# SCH_gravmaskin_mottagare_2024-06-04.net
KiCad netlist of a schematic drawn in EasyEDA
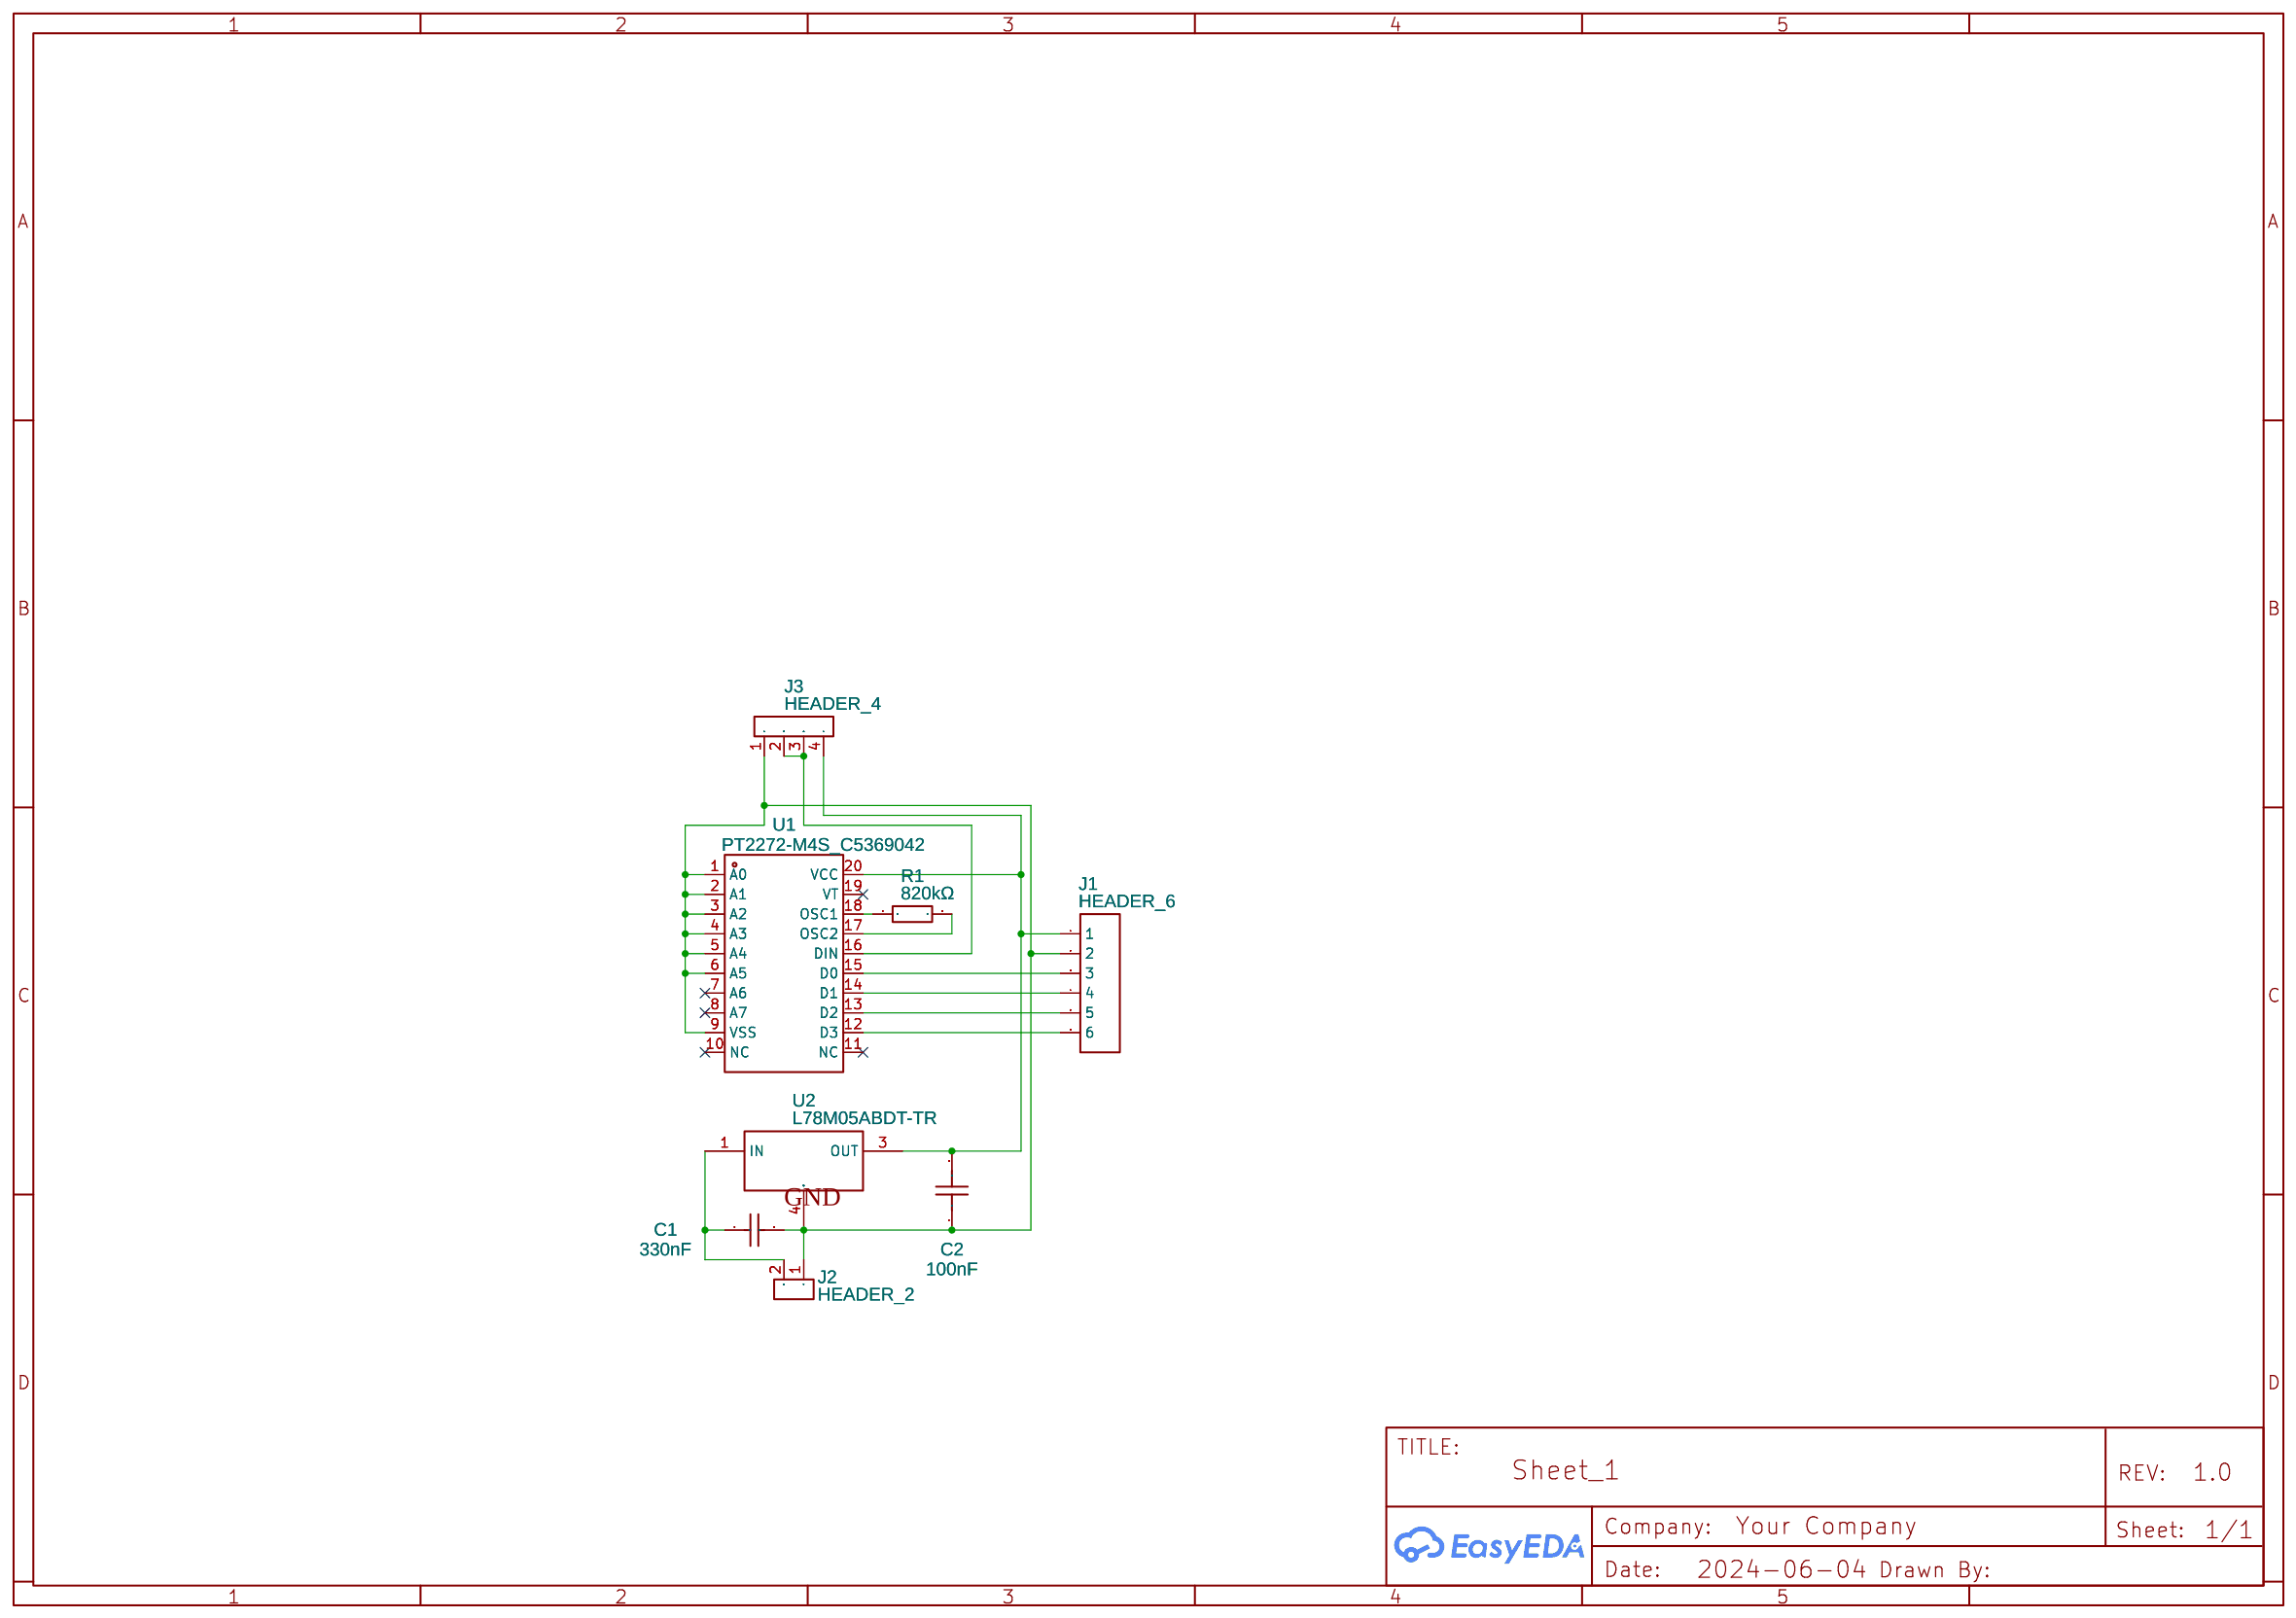
[diagram p0: schematic sheet]

(export (version "E")
  (design (tool "Eeschema 10.0.6"))
  (components
    (comp (ref "C1")
      (value "330nF")
      (fields (field (name "Manufacturer Part") "0603B334K250NT") (field (name "Manufacturer") "FH(风华)"))
      (libsource (lib "") (part "0603B334K250NT"))
    )
    (comp (ref "C2")
      (value "100nF")
      (fields
        (field (name "Manufacturer Part") "CC0603KRX7R9BB104")
        (field (name "Manufacturer") "YAGEO(国巨)")
      )
      (libsource (lib "") (part "CC0603KRX7R9BB104"))
    )
    (comp (ref "J1") (value "HEADER_6") (libsource (lib "") (part "HEADER_6")))
    (comp (ref "J2") (value "HEADER_2") (libsource (lib "") (part "HEADER_2")))
    (comp (ref "J3") (value "HEADER_4") (libsource (lib "") (part "HEADER_4")))
    (comp (ref "R1")
      (value "820kΩ")
      (fields (field (name "Manufacturer Part") "RC-01W824JT") (field (name "Manufacturer") "FH(风华)"))
      (libsource (lib "") (part "RC-01W824JT"))
    )
    (comp (ref "U1")
      (value "PT2272-M4S_C5369042")
      (fields (field (name "Manufacturer Part") "PT2272-M4S") (field (name "Manufacturer") "PTC(普诚)"))
      (libsource (lib "") (part "PT2272-M4S_C5369042"))
    )
    (comp (ref "U2")
      (value "L78M05ABDT-TR")
      (fields (field (name "Manufacturer") "ST(意法半导体)"))
      (libsource (lib "") (part "L78M05ABDT-TR"))
    )
  )
  (nets
    (net (code "1") (name "Net-(U1-A0)") (class "Default")
      (node (ref "C1") (pin "1") (pinfunction "1_1") (pintype "input"))
      (node (ref "C2") (pin "1") (pinfunction "1_1") (pintype "unspecified"))
      (node (ref "J1") (pin "2") (pinfunction "2_2") (pintype "input"))
      (node (ref "J2") (pin "1") (pinfunction "1_1") (pintype "unspecified"))
      (node (ref "J3") (pin "1") (pinfunction "1_1") (pintype "unspecified"))
      (node (ref "U1") (pin "1") (pinfunction "A0_1") (pintype "unspecified"))
      (node (ref "U1") (pin "2") (pinfunction "A1_2") (pintype "unspecified"))
      (node (ref "U1") (pin "3") (pinfunction "A2_3") (pintype "unspecified"))
      (node (ref "U1") (pin "4") (pinfunction "A3_4") (pintype "unspecified"))
      (node (ref "U1") (pin "5") (pinfunction "A4_5") (pintype "unspecified"))
      (node (ref "U1") (pin "6") (pinfunction "A5_6") (pintype "unspecified"))
      (node (ref "U1") (pin "9") (pinfunction "VSS_9") (pintype "unspecified"))
      (node (ref "U2") (pin "4") (pinfunction "GND_4") (pintype "passive"))
    )
    (net (code "2") (name "Net-(U1-D0)") (class "Default")
      (node (ref "J1") (pin "3") (pinfunction "3_3") (pintype "input"))
      (node (ref "U1") (pin "15") (pinfunction "D0_15") (pintype "unspecified"))
    )
    (net (code "3") (name "Net-(U1-D1)") (class "Default")
      (node (ref "J1") (pin "4") (pinfunction "4_4") (pintype "input"))
      (node (ref "U1") (pin "14") (pinfunction "D1_14") (pintype "unspecified"))
    )
    (net (code "4") (name "Net-(U1-D2)") (class "Default")
      (node (ref "J1") (pin "5") (pinfunction "5_5") (pintype "input"))
      (node (ref "U1") (pin "13") (pinfunction "D2_13") (pintype "unspecified"))
    )
    (net (code "5") (name "Net-(U1-D3)") (class "Default")
      (node (ref "J1") (pin "6") (pinfunction "6_6") (pintype "input"))
      (node (ref "U1") (pin "12") (pinfunction "D3_12") (pintype "unspecified"))
    )
    (net (code "6") (name "Net-(U1-DIN)") (class "Default")
      (node (ref "J3") (pin "2") (pinfunction "2_2") (pintype "unspecified"))
      (node (ref "J3") (pin "3") (pinfunction "3_3") (pintype "unspecified"))
      (node (ref "U1") (pin "16") (pinfunction "DIN_16") (pintype "unspecified"))
    )
    (net (code "7") (name "Net-(U1-OSC1)") (class "Default")
      (node (ref "R1") (pin "1") (pinfunction "1_1") (pintype "unspecified"))
      (node (ref "U1") (pin "18") (pinfunction "OSC1_18") (pintype "unspecified"))
    )
    (net (code "8") (name "Net-(U1-OSC2)") (class "Default")
      (node (ref "R1") (pin "2") (pinfunction "2_2") (pintype "unspecified"))
      (node (ref "U1") (pin "17") (pinfunction "OSC2_17") (pintype "unspecified"))
    )
    (net (code "9") (name "Net-(U1-VCC)") (class "Default")
      (node (ref "C2") (pin "2") (pinfunction "2_2") (pintype "unspecified"))
      (node (ref "J1") (pin "1") (pinfunction "1_1") (pintype "input"))
      (node (ref "J3") (pin "4") (pinfunction "4_4") (pintype "unspecified"))
      (node (ref "U1") (pin "20") (pinfunction "VCC_20") (pintype "unspecified"))
      (node (ref "U2") (pin "3") (pinfunction "OUT_3") (pintype "passive"))
    )
    (net (code "10") (name "Net-(U2-IN)") (class "Default")
      (node (ref "C1") (pin "2") (pinfunction "2_2") (pintype "input"))
      (node (ref "J2") (pin "2") (pinfunction "2_2") (pintype "unspecified"))
      (node (ref "U2") (pin "1") (pinfunction "IN_1") (pintype "passive"))
    )
    (net (code "11") (name "unconnected-(U1-A6-Pad7)") (class "Default")
      (node (ref "U1") (pin "7") (pinfunction "A6_7") (pintype "unspecified+no_connect"))
    )
    (net (code "12") (name "unconnected-(U1-A7-Pad8)") (class "Default")
      (node (ref "U1") (pin "8") (pinfunction "A7_8") (pintype "unspecified+no_connect"))
    )
    (net (code "13") (name "unconnected-(U1-NC-Pad10)") (class "Default")
      (node (ref "U1") (pin "10") (pinfunction "NC_10") (pintype "unspecified+no_connect"))
    )
    (net (code "14") (name "unconnected-(U1-NC-Pad11)") (class "Default")
      (node (ref "U1") (pin "11") (pinfunction "NC_11") (pintype "unspecified+no_connect"))
    )
    (net (code "15") (name "unconnected-(U1-VT-Pad19)") (class "Default")
      (node (ref "U1") (pin "19") (pinfunction "VT_19") (pintype "unspecified+no_connect"))
    )
  )
)
